# LC_LPF8.net
KiCad netlist of a schematic drawn in Altium Designer
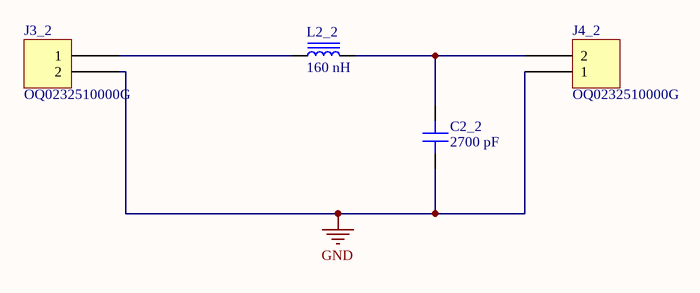
[diagram p0: LC_LPF8.SchDoc]

(export (version "E")
  (design (tool "Eeschema 10.0.6"))
  (components
    (comp (ref "C2_2")
      (value "2700 pF")
      (footprint "CAP 0603_1608")
      (description "CAP CER 2700PF 25V NP0 0603")
      (fields (field (name "PART NUMBER") "C0603C272F3GAC7867") (field (name "MANUFACTURER") "KEMET"))
      (libsource (lib "Celestial Altium Library - altium_library") (part "Capacitor"))
    )
    (comp (ref "J3_2")
      (value "OQ0232510000G")
      (footprint "FCI 06-381-2PIN")
      (description "TERM BLOCK HDR 2POS 90DEG 3.81MM")
      (fields (field (name "MANUFACTURER") "Amphenol Anytek"))
      (libsource (lib "Celestial Altium Library - altium_library") (part "2 Pin"))
    )
    (comp (ref "J4_2")
      (value "OQ0232510000G")
      (footprint "FCI 06-381-2PIN")
      (description "TERM BLOCK HDR 2POS 90DEG 3.81MM")
      (fields (field (name "MANUFACTURER") "Amphenol Anytek"))
      (libsource (lib "") (part "2 Pin_1"))
    )
    (comp (ref "L2_2")
      (value "160 nH")
      (footprint "IND 0402_1005 RF WW")
      (description "FIXED IND 160NH 480MA 330MOHM SM")
      (fields
        (field (name "PART NUMBER") "LQW15CNR16J00D")
        (field (name "MANUFACTURER") "Murata Electronics")
      )
      (libsource (lib "Celestial Altium Library - altium_library") (part "Inductor"))
    )
  )
  (nets
    (net (code "1") (name "GND") (class "Default")
      (node (ref "C2_2") (pin "1") (pinfunction "1_1") (pintype "passive"))
      (node (ref "J3_2") (pin "2") (pinfunction "2_2") (pintype "passive"))
      (node (ref "J4_2") (pin "1") (pinfunction "1_1") (pintype "passive"))
    )
    (net (code "2") (name "Net-(C2_2-Pad2)") (class "Default")
      (node (ref "C2_2") (pin "2") (pinfunction "2_2") (pintype "passive"))
      (node (ref "J4_2") (pin "2") (pinfunction "2_2") (pintype "passive"))
      (node (ref "L2_2") (pin "2") (pinfunction "2_2") (pintype "passive"))
    )
    (net (code "3") (name "Net-(J3_2-Pad1)") (class "Default")
      (node (ref "J3_2") (pin "1") (pinfunction "1_1") (pintype "passive"))
      (node (ref "L2_2") (pin "1") (pinfunction "1_1") (pintype "passive"))
    )
  )
)
